# STM32F4.net
KiCad netlist of a schematic drawn in Altium Designer
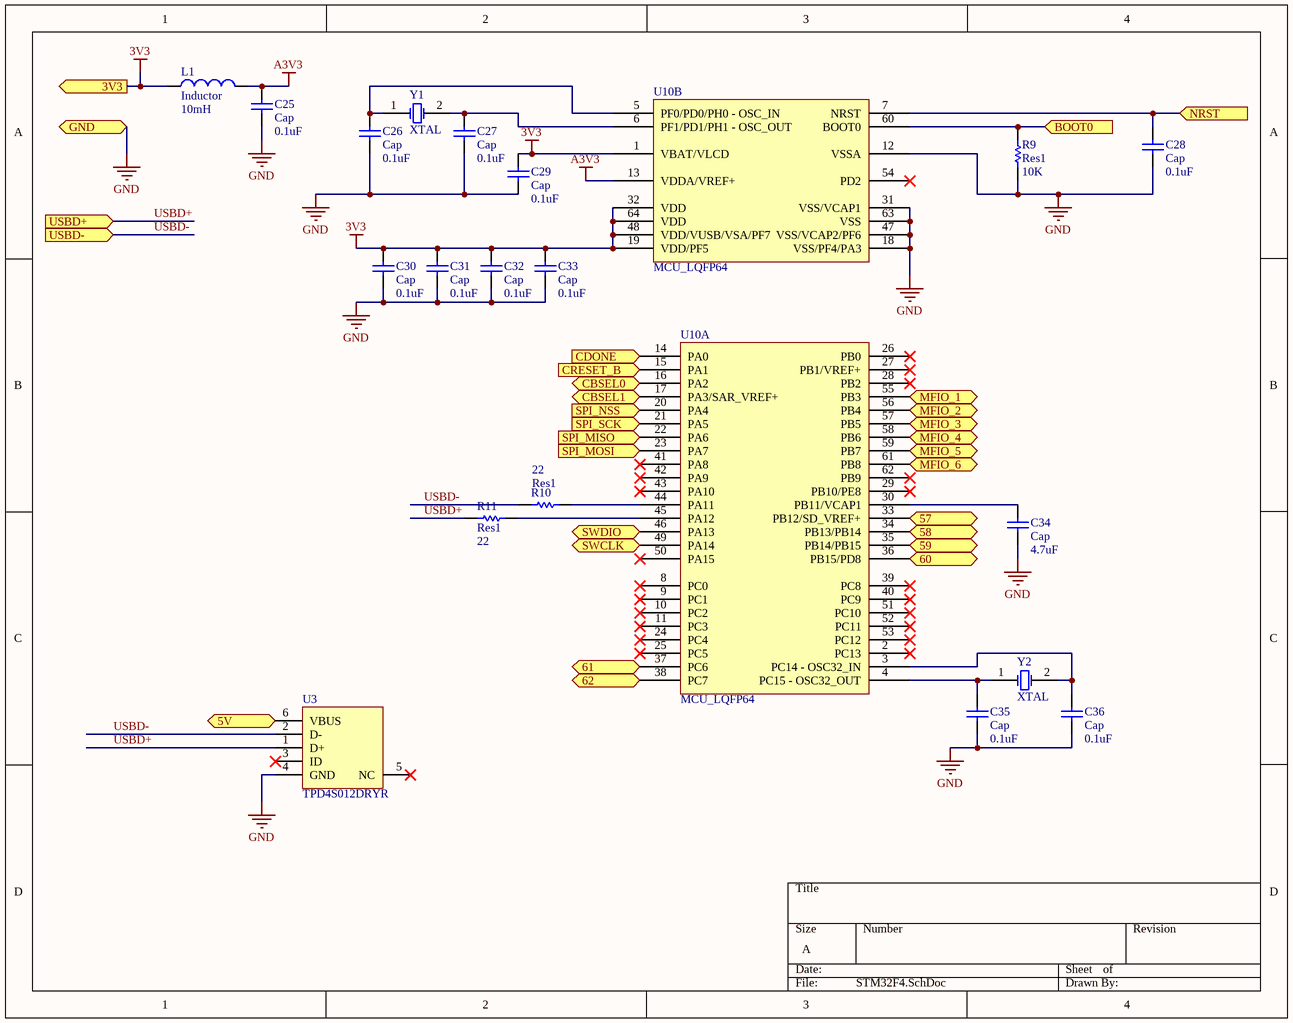
[diagram p0: STM32F4.SchDoc]

(export (version "E")
  (design (tool "Eeschema 10.0.6"))
  (components
    (comp (ref "C25")
      (value "Cap")
      (footprint "RAD-0.3")
      (description "Capacitor")
      (fields (field (name "ALTIUM_VALUE") "0.1uF") (field (name "PUBLISHER") "Altium Limited"))
      (libsource (lib "Miscellaneous Devices") (part "Cap"))
    )
    (comp (ref "C26")
      (value "Cap")
      (footprint "RAD-0.3")
      (description "Capacitor")
      (fields (field (name "ALTIUM_VALUE") "0.1uF") (field (name "PUBLISHER") "Altium Limited"))
      (libsource (lib "Miscellaneous Devices") (part "Cap"))
    )
    (comp (ref "C27")
      (value "Cap")
      (footprint "RAD-0.3")
      (description "Capacitor")
      (fields (field (name "ALTIUM_VALUE") "0.1uF") (field (name "PUBLISHER") "Altium Limited"))
      (libsource (lib "Miscellaneous Devices") (part "Cap"))
    )
    (comp (ref "C28")
      (value "Cap")
      (footprint "RAD-0.3")
      (description "Capacitor")
      (fields (field (name "ALTIUM_VALUE") "0.1uF") (field (name "PUBLISHER") "Altium Limited"))
      (libsource (lib "Miscellaneous Devices") (part "Cap"))
    )
    (comp (ref "C29")
      (value "Cap")
      (footprint "RAD-0.3")
      (description "Capacitor")
      (fields (field (name "ALTIUM_VALUE") "0.1uF") (field (name "PUBLISHER") "Altium Limited"))
      (libsource (lib "Miscellaneous Devices") (part "Cap"))
    )
    (comp (ref "C30")
      (value "Cap")
      (footprint "RAD-0.3")
      (description "Capacitor")
      (fields (field (name "ALTIUM_VALUE") "0.1uF") (field (name "PUBLISHER") "Altium Limited"))
      (libsource (lib "Miscellaneous Devices") (part "Cap"))
    )
    (comp (ref "C31")
      (value "Cap")
      (footprint "RAD-0.3")
      (description "Capacitor")
      (fields (field (name "ALTIUM_VALUE") "0.1uF") (field (name "PUBLISHER") "Altium Limited"))
      (libsource (lib "Miscellaneous Devices") (part "Cap"))
    )
    (comp (ref "C32")
      (value "Cap")
      (footprint "RAD-0.3")
      (description "Capacitor")
      (fields (field (name "ALTIUM_VALUE") "0.1uF") (field (name "PUBLISHER") "Altium Limited"))
      (libsource (lib "Miscellaneous Devices") (part "Cap"))
    )
    (comp (ref "C33")
      (value "Cap")
      (footprint "RAD-0.3")
      (description "Capacitor")
      (fields (field (name "ALTIUM_VALUE") "0.1uF") (field (name "PUBLISHER") "Altium Limited"))
      (libsource (lib "Miscellaneous Devices") (part "Cap"))
    )
    (comp (ref "C34")
      (value "Cap")
      (footprint "RAD-0.3")
      (description "Capacitor")
      (fields (field (name "ALTIUM_VALUE") "4.7uF") (field (name "PUBLISHER") "Altium Limited"))
      (libsource (lib "Miscellaneous Devices") (part "Cap"))
    )
    (comp (ref "C35")
      (value "Cap")
      (footprint "RAD-0.3")
      (description "Capacitor")
      (fields (field (name "ALTIUM_VALUE") "0.1uF") (field (name "PUBLISHER") "Altium Limited"))
      (libsource (lib "Miscellaneous Devices") (part "Cap"))
    )
    (comp (ref "C36")
      (value "Cap")
      (footprint "RAD-0.3")
      (description "Capacitor")
      (fields (field (name "ALTIUM_VALUE") "0.1uF") (field (name "PUBLISHER") "Altium Limited"))
      (libsource (lib "Miscellaneous Devices") (part "Cap"))
    )
    (comp (ref "L1")
      (value "Inductor")
      (footprint "0402-A")
      (fields (field (name "ALTIUM_VALUE") "10mH") (field (name "PUBLISHER") "Altium Limited"))
      (libsource (lib "Miscellaneous Devices") (part "Inductor"))
    )
    (comp (ref "R9")
      (value "Res1")
      (footprint "AXIAL-0.3")
      (description "Resistor")
      (fields (field (name "ALTIUM_VALUE") "10K") (field (name "PUBLISHER") "Altium Limited"))
      (libsource (lib "Miscellaneous Devices") (part "Res1"))
    )
    (comp (ref "R10")
      (value "Res1")
      (footprint "AXIAL-0.3")
      (description "Resistor")
      (fields (field (name "ALTIUM_VALUE") "22") (field (name "PUBLISHER") "Altium Limited"))
      (libsource (lib "Miscellaneous Devices") (part "Res1"))
    )
    (comp (ref "R11")
      (value "Res1")
      (footprint "AXIAL-0.3")
      (description "Resistor")
      (fields (field (name "ALTIUM_VALUE") "22") (field (name "PUBLISHER") "Altium Limited"))
      (libsource (lib "Miscellaneous Devices") (part "Res1"))
    )
    (comp (ref "U3")
      (value "TPD4S012DRYR")
      (footprint "DRY6")
      (fields (field (name "MANUFACTURER") "Texas Instruments"))
      (libsource (lib "TI Interface ESD EMI Protection") (part "TPD4S012DRYR"))
    )
    (comp (ref "U10")
      (value "MCU_LQFP64")
      (footprint "STM-LQFP64_M")
      (libsource (lib "MB1136") (part "MCU_LQFP64"))
    )
    (comp (ref "Y1")
      (value "XTAL")
      (footprint "R38")
      (description "Crystal Oscillator")
      (fields (field (name "PUBLISHER") "Altium Limited"))
      (libsource (lib "Miscellaneous Devices") (part "XTAL"))
    )
    (comp (ref "Y2")
      (value "XTAL")
      (footprint "R38")
      (description "Crystal Oscillator")
      (fields (field (name "PUBLISHER") "Altium Limited"))
      (libsource (lib "Miscellaneous Devices") (part "XTAL"))
    )
  )
  (nets
    (net (code "1") (name "/5V") (class "Default")
      (node (ref "U3") (pin "6") (pinfunction "VBUS_6") (pintype "passive"))
    )
    (net (code "2") (name "/57") (class "Default")
      (node (ref "U10") (pin "33") (pinfunction "PB12/SD_VREF+_33") (pintype "passive"))
    )
    (net (code "3") (name "/58") (class "Default")
      (node (ref "U10") (pin "34") (pinfunction "PB13/PB14_34") (pintype "passive"))
    )
    (net (code "4") (name "/59") (class "Default")
      (node (ref "U10") (pin "35") (pinfunction "PB14/PB15_35") (pintype "passive"))
    )
    (net (code "5") (name "/60") (class "Default")
      (node (ref "U10") (pin "36") (pinfunction "PB15/PD8_36") (pintype "passive"))
    )
    (net (code "6") (name "/61") (class "Default")
      (node (ref "U10") (pin "37") (pinfunction "PC6_37") (pintype "passive"))
    )
    (net (code "7") (name "/62") (class "Default")
      (node (ref "U10") (pin "38") (pinfunction "PC7_38") (pintype "passive"))
    )
    (net (code "8") (name "/BOOT0") (class "Default")
      (node (ref "R9") (pin "2") (pinfunction "2_2") (pintype "passive"))
      (node (ref "U10") (pin "60") (pinfunction "BOOT0_60") (pintype "passive"))
    )
    (net (code "9") (name "/CBSEL0") (class "Default")
      (node (ref "U10") (pin "16") (pinfunction "PA2_16") (pintype "passive"))
    )
    (net (code "10") (name "/CBSEL1") (class "Default")
      (node (ref "U10") (pin "17") (pinfunction "PA3/SAR_VREF+_17") (pintype "passive"))
    )
    (net (code "11") (name "/CDONE") (class "Default")
      (node (ref "U10") (pin "14") (pinfunction "PA0_14") (pintype "passive"))
    )
    (net (code "12") (name "/CRESET_B") (class "Default")
      (node (ref "U10") (pin "15") (pinfunction "PA1_15") (pintype "passive"))
    )
    (net (code "13") (name "/MFIO_1") (class "Default")
      (node (ref "U10") (pin "55") (pinfunction "PB3_55") (pintype "passive"))
    )
    (net (code "14") (name "/MFIO_2") (class "Default")
      (node (ref "U10") (pin "56") (pinfunction "PB4_56") (pintype "passive"))
    )
    (net (code "15") (name "/MFIO_3") (class "Default")
      (node (ref "U10") (pin "57") (pinfunction "PB5_57") (pintype "passive"))
    )
    (net (code "16") (name "/MFIO_4") (class "Default")
      (node (ref "U10") (pin "58") (pinfunction "PB6_58") (pintype "passive"))
    )
    (net (code "17") (name "/MFIO_5") (class "Default")
      (node (ref "U10") (pin "59") (pinfunction "PB7_59") (pintype "passive"))
    )
    (net (code "18") (name "/MFIO_6") (class "Default")
      (node (ref "U10") (pin "61") (pinfunction "PB8_61") (pintype "passive"))
    )
    (net (code "19") (name "/NRST") (class "Default")
      (node (ref "C28") (pin "1") (pinfunction "1_1") (pintype "passive"))
      (node (ref "U10") (pin "7") (pinfunction "NRST_7") (pintype "passive"))
    )
    (net (code "20") (name "/SPI_MISO") (class "Default")
      (node (ref "U10") (pin "22") (pinfunction "PA6_22") (pintype "passive"))
    )
    (net (code "21") (name "/SPI_MOSI") (class "Default")
      (node (ref "U10") (pin "23") (pinfunction "PA7_23") (pintype "passive"))
    )
    (net (code "22") (name "/SPI_NSS") (class "Default")
      (node (ref "U10") (pin "20") (pinfunction "PA4_20") (pintype "passive"))
    )
    (net (code "23") (name "/SPI_SCK") (class "Default")
      (node (ref "U10") (pin "21") (pinfunction "PA5_21") (pintype "passive"))
    )
    (net (code "24") (name "/SWCLK") (class "Default")
      (node (ref "U10") (pin "49") (pinfunction "PA14_49") (pintype "passive"))
    )
    (net (code "25") (name "/SWDIO") (class "Default")
      (node (ref "U10") (pin "46") (pinfunction "PA13_46") (pintype "passive"))
    )
    (net (code "26") (name "/USBD+") (class "Default")
      (node (ref "R11") (pin "2") (pinfunction "2_2") (pintype "passive"))
      (node (ref "U3") (pin "1") (pinfunction "D+_1") (pintype "passive"))
    )
    (net (code "27") (name "/USBD-") (class "Default")
      (node (ref "R10") (pin "2") (pinfunction "2_2") (pintype "passive"))
      (node (ref "U3") (pin "2") (pinfunction "D-_2") (pintype "passive"))
    )
    (net (code "28") (name "3V3") (class "Default")
      (node (ref "C29") (pin "1") (pinfunction "1_1") (pintype "passive"))
      (node (ref "C30") (pin "1") (pinfunction "1_1") (pintype "passive"))
      (node (ref "C31") (pin "1") (pinfunction "1_1") (pintype "passive"))
      (node (ref "C32") (pin "1") (pinfunction "1_1") (pintype "passive"))
      (node (ref "C33") (pin "1") (pinfunction "1_1") (pintype "passive"))
      (node (ref "L1") (pin "1") (pinfunction "1_1") (pintype "passive"))
      (node (ref "U10") (pin "1") (pinfunction "VBAT/VLCD_1") (pintype "passive"))
      (node (ref "U10") (pin "19") (pinfunction "VDD/PF5_19") (pintype "passive"))
      (node (ref "U10") (pin "32") (pinfunction "VDD_32") (pintype "passive"))
      (node (ref "U10") (pin "48") (pinfunction "VDD/VUSB/VSA/PF7_48") (pintype "passive"))
      (node (ref "U10") (pin "64") (pinfunction "VDD_64") (pintype "passive"))
    )
    (net (code "29") (name "A3V3") (class "Default")
      (node (ref "C25") (pin "1") (pinfunction "1_1") (pintype "passive"))
      (node (ref "L1") (pin "2") (pinfunction "2_2") (pintype "passive"))
      (node (ref "U10") (pin "13") (pinfunction "VDDA/VREF+_13") (pintype "passive"))
    )
    (net (code "30") (name "GND") (class "Default")
      (node (ref "C25") (pin "2") (pinfunction "2_2") (pintype "passive"))
      (node (ref "C26") (pin "2") (pinfunction "2_2") (pintype "passive"))
      (node (ref "C27") (pin "2") (pinfunction "2_2") (pintype "passive"))
      (node (ref "C28") (pin "2") (pinfunction "2_2") (pintype "passive"))
      (node (ref "C29") (pin "2") (pinfunction "2_2") (pintype "passive"))
      (node (ref "C30") (pin "2") (pinfunction "2_2") (pintype "passive"))
      (node (ref "C31") (pin "2") (pinfunction "2_2") (pintype "passive"))
      (node (ref "C32") (pin "2") (pinfunction "2_2") (pintype "passive"))
      (node (ref "C33") (pin "2") (pinfunction "2_2") (pintype "passive"))
      (node (ref "C34") (pin "2") (pinfunction "2_2") (pintype "passive"))
      (node (ref "C35") (pin "2") (pinfunction "2_2") (pintype "passive"))
      (node (ref "C36") (pin "2") (pinfunction "2_2") (pintype "passive"))
      (node (ref "R9") (pin "1") (pinfunction "1_1") (pintype "passive"))
      (node (ref "U10") (pin "12") (pinfunction "VSSA_12") (pintype "passive"))
      (node (ref "U10") (pin "18") (pinfunction "VSS/PF4/PA3_18") (pintype "passive"))
      (node (ref "U10") (pin "31") (pinfunction "VSS/VCAP1_31") (pintype "passive"))
      (node (ref "U10") (pin "47") (pinfunction "VSS/VCAP2/PF6_47") (pintype "passive"))
      (node (ref "U10") (pin "63") (pinfunction "VSS_63") (pintype "passive"))
      (node (ref "U3") (pin "4") (pinfunction "GND_4") (pintype "power_in"))
    )
    (net (code "31") (name "Net-(U10A-PA11)") (class "Default")
      (node (ref "R10") (pin "1") (pinfunction "1_1") (pintype "passive"))
      (node (ref "U10") (pin "44") (pinfunction "PA11_44") (pintype "passive"))
    )
    (net (code "32") (name "Net-(U10A-PA12)") (class "Default")
      (node (ref "R11") (pin "1") (pinfunction "1_1") (pintype "passive"))
      (node (ref "U10") (pin "45") (pinfunction "PA12_45") (pintype "passive"))
    )
    (net (code "33") (name "Net-(U10A-PB11{slash}VCAP1)") (class "Default")
      (node (ref "C34") (pin "1") (pinfunction "1_1") (pintype "passive"))
      (node (ref "U10") (pin "30") (pinfunction "PB11/VCAP1_30") (pintype "passive"))
    )
    (net (code "34") (name "Net-(U10A-PC14_-_OSC32_IN)") (class "Default")
      (node (ref "C36") (pin "1") (pinfunction "1_1") (pintype "passive"))
      (node (ref "U10") (pin "3") (pinfunction "PC14_-_OSC32_IN_3") (pintype "passive"))
      (node (ref "Y2") (pin "2") (pinfunction "OSC2_2") (pintype "passive"))
    )
    (net (code "35") (name "Net-(U10A-PC15_-_OSC32_OUT)") (class "Default")
      (node (ref "C35") (pin "1") (pinfunction "1_1") (pintype "passive"))
      (node (ref "U10") (pin "4") (pinfunction "PC15_-_OSC32_OUT_4") (pintype "passive"))
      (node (ref "Y2") (pin "1") (pinfunction "OSC1_1") (pintype "passive"))
    )
    (net (code "36") (name "Net-(U10B-PF0{slash}PD0{slash}PH0_-_OSC_IN)") (class "Default")
      (node (ref "C26") (pin "1") (pinfunction "1_1") (pintype "passive"))
      (node (ref "U10") (pin "5") (pinfunction "PF0/PD0/PH0_-_OSC_IN_5") (pintype "passive"))
      (node (ref "Y1") (pin "1") (pinfunction "OSC1_1") (pintype "passive"))
    )
    (net (code "37") (name "Net-(U10B-PF1{slash}PD1{slash}PH1_-_OSC_OUT)") (class "Default")
      (node (ref "C27") (pin "1") (pinfunction "1_1") (pintype "passive"))
      (node (ref "U10") (pin "6") (pinfunction "PF1/PD1/PH1_-_OSC_OUT_6") (pintype "passive"))
      (node (ref "Y1") (pin "2") (pinfunction "OSC2_2") (pintype "passive"))
    )
    (net (code "38") (name "unconnected-(U3-ID-Pad3)") (class "Default")
      (node (ref "U3") (pin "3") (pinfunction "ID_3") (pintype "passive+no_connect"))
    )
    (net (code "39") (name "unconnected-(U3-NC-Pad5)") (class "Default")
      (node (ref "U3") (pin "5") (pinfunction "NC_5") (pintype "passive+no_connect"))
    )
    (net (code "40") (name "unconnected-(U10A-PA8-Pad41)") (class "Default")
      (node (ref "U10") (pin "41") (pinfunction "PA8_41") (pintype "passive+no_connect"))
    )
    (net (code "41") (name "unconnected-(U10A-PA9-Pad42)") (class "Default")
      (node (ref "U10") (pin "42") (pinfunction "PA9_42") (pintype "passive+no_connect"))
    )
    (net (code "42") (name "unconnected-(U10A-PA10-Pad43)") (class "Default")
      (node (ref "U10") (pin "43") (pinfunction "PA10_43") (pintype "passive+no_connect"))
    )
    (net (code "43") (name "unconnected-(U10A-PA15-Pad50)") (class "Default")
      (node (ref "U10") (pin "50") (pinfunction "PA15_50") (pintype "passive+no_connect"))
    )
    (net (code "44") (name "unconnected-(U10A-PB0-Pad26)") (class "Default")
      (node (ref "U10") (pin "26") (pinfunction "PB0_26") (pintype "passive+no_connect"))
    )
    (net (code "45") (name "unconnected-(U10A-PB1{slash}VREF+-Pad27)") (class "Default")
      (node (ref "U10") (pin "27") (pinfunction "PB1/VREF+_27") (pintype "passive+no_connect"))
    )
    (net (code "46") (name "unconnected-(U10A-PB2-Pad28)") (class "Default")
      (node (ref "U10") (pin "28") (pinfunction "PB2_28") (pintype "passive+no_connect"))
    )
    (net (code "47") (name "unconnected-(U10A-PB9-Pad62)") (class "Default")
      (node (ref "U10") (pin "62") (pinfunction "PB9_62") (pintype "passive+no_connect"))
    )
    (net (code "48") (name "unconnected-(U10A-PB10{slash}PE8-Pad29)") (class "Default")
      (node (ref "U10") (pin "29") (pinfunction "PB10/PE8_29") (pintype "passive+no_connect"))
    )
    (net (code "49") (name "unconnected-(U10A-PC0-Pad8)") (class "Default")
      (node (ref "U10") (pin "8") (pinfunction "PC0_8") (pintype "passive+no_connect"))
    )
    (net (code "50") (name "unconnected-(U10A-PC1-Pad9)") (class "Default")
      (node (ref "U10") (pin "9") (pinfunction "PC1_9") (pintype "passive+no_connect"))
    )
    (net (code "51") (name "unconnected-(U10A-PC2-Pad10)") (class "Default")
      (node (ref "U10") (pin "10") (pinfunction "PC2_10") (pintype "passive+no_connect"))
    )
    (net (code "52") (name "unconnected-(U10A-PC3-Pad11)") (class "Default")
      (node (ref "U10") (pin "11") (pinfunction "PC3_11") (pintype "passive+no_connect"))
    )
    (net (code "53") (name "unconnected-(U10A-PC4-Pad24)") (class "Default")
      (node (ref "U10") (pin "24") (pinfunction "PC4_24") (pintype "passive+no_connect"))
    )
    (net (code "54") (name "unconnected-(U10A-PC5-Pad25)") (class "Default")
      (node (ref "U10") (pin "25") (pinfunction "PC5_25") (pintype "passive+no_connect"))
    )
    (net (code "55") (name "unconnected-(U10A-PC8-Pad39)") (class "Default")
      (node (ref "U10") (pin "39") (pinfunction "PC8_39") (pintype "passive+no_connect"))
    )
    (net (code "56") (name "unconnected-(U10A-PC9-Pad40)") (class "Default")
      (node (ref "U10") (pin "40") (pinfunction "PC9_40") (pintype "passive+no_connect"))
    )
    (net (code "57") (name "unconnected-(U10A-PC10-Pad51)") (class "Default")
      (node (ref "U10") (pin "51") (pinfunction "PC10_51") (pintype "passive+no_connect"))
    )
    (net (code "58") (name "unconnected-(U10A-PC11-Pad52)") (class "Default")
      (node (ref "U10") (pin "52") (pinfunction "PC11_52") (pintype "passive+no_connect"))
    )
    (net (code "59") (name "unconnected-(U10A-PC12-Pad53)") (class "Default")
      (node (ref "U10") (pin "53") (pinfunction "PC12_53") (pintype "passive+no_connect"))
    )
    (net (code "60") (name "unconnected-(U10A-PC13-Pad2)") (class "Default")
      (node (ref "U10") (pin "2") (pinfunction "PC13_2") (pintype "passive+no_connect"))
    )
    (net (code "61") (name "unconnected-(U10B-PD2-Pad54)") (class "Default")
      (node (ref "U10") (pin "54") (pinfunction "PD2_54") (pintype "passive+no_connect"))
    )
  )
)
